# Main_Scheme.net
KiCad netlist of a schematic drawn in Altium Designer
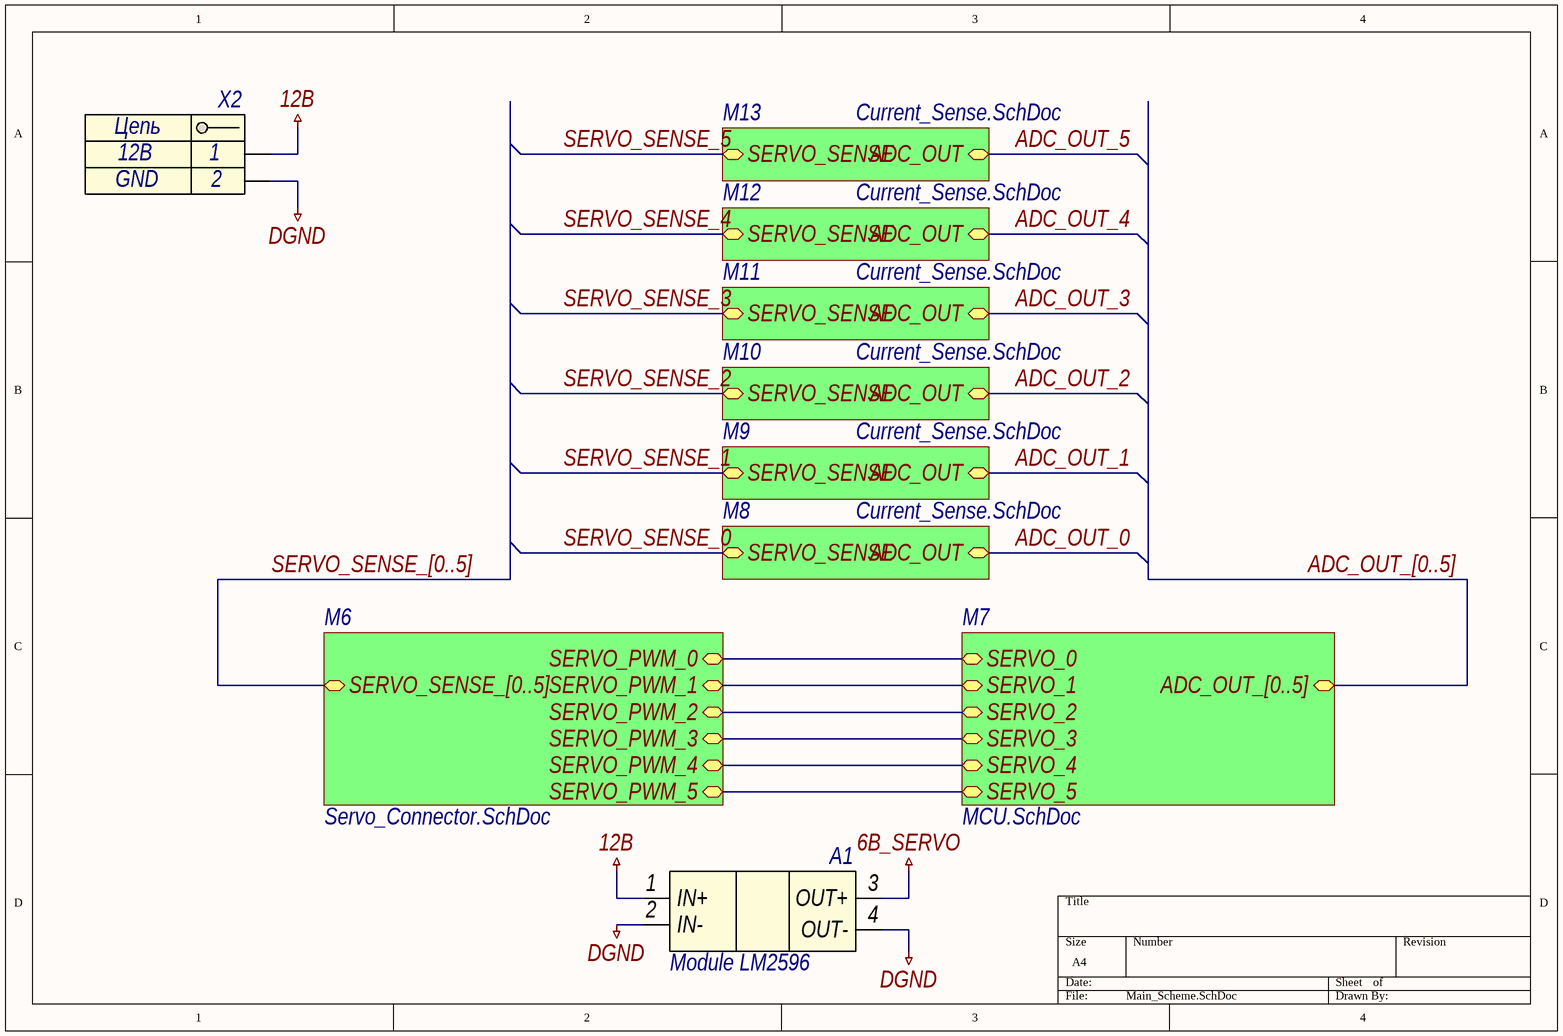
[diagram p0: Main_Scheme.SchDoc]

(export (version "E")
  (design (tool "Eeschema 10.0.6"))
  (components
    (comp (ref "A1")
      (value "Module LM2596")
      (footprint "module LM2596")
      (description "Low-Dropout Regulator for 5-V to 3.3-V Conversion")
      (libsource (lib "MOP44") (part "Module LM2596"))
    )
    (comp (ref "X2")
      (value "Header_2_trm")
      (footprint "TERMINAL-2WAY-3.5MM")
      (description "Разъем - 2 конт. клеммник")
      (libsource (lib "MOP44") (part "Header_2_trm"))
    )
  )
  (nets
    (net (code "21") (name "6В_SERVO") (class "Default")
      (node (ref "A1") (pin "3") (pinfunction "OUT+_3") (pintype "power_in"))
    )
    (net (code "22") (name "12В") (class "Default")
      (node (ref "A1") (pin "1") (pinfunction "IN+_1") (pintype "power_in"))
      (node (ref "X2") (pin "1") (pinfunction "1_1") (pintype "passive"))
    )
    (net (code "23") (name "DGND") (class "Default")
      (node (ref "A1") (pin "2") (pinfunction "IN-_2") (pintype "power_in"))
      (node (ref "A1") (pin "4") (pinfunction "OUT-_4") (pintype "power_in"))
      (node (ref "X2") (pin "2") (pinfunction "2_2") (pintype "passive"))
    )
  )
)
